# podstawa.net
KiCad netlist of a schematic drawn in EAGLE
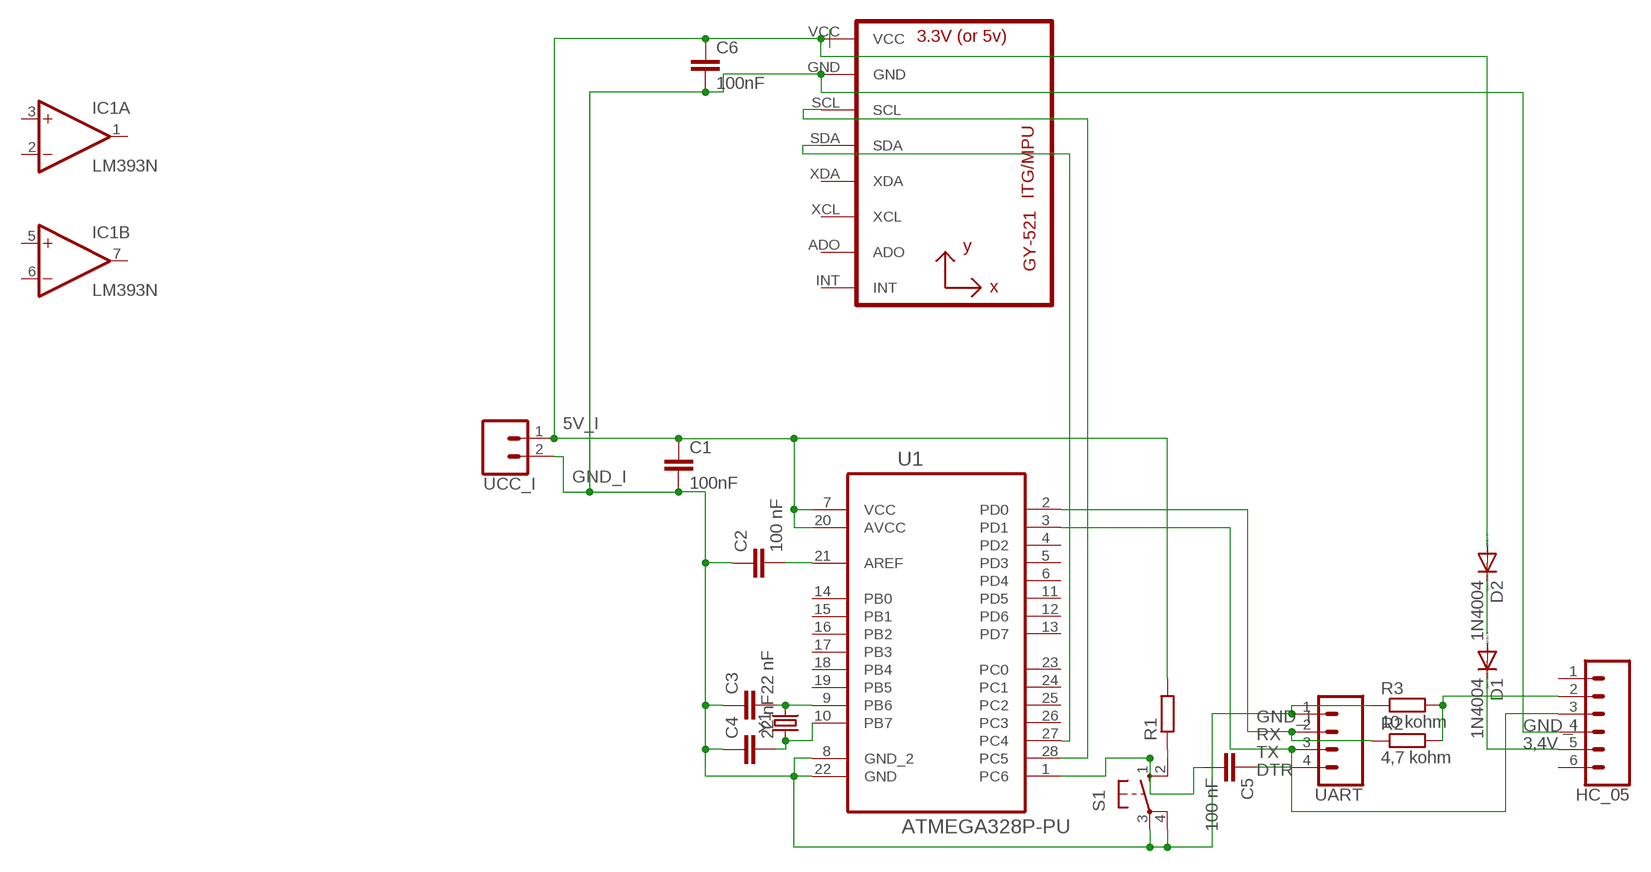
[diagram p0: schematic, sheet 1]

(export (version "E")
  (design (tool "Eeschema 10.0.6"))
  (components
    (comp (ref "C1")
      (value "100nF")
      (footprint "eagle-import:C025-030X050")
      (libsource (lib "eagle-import") (part "C-EU025-030X050"))
    )
    (comp (ref "C2")
      (value "100 nF")
      (footprint "eagle-import:C025-030X050")
      (libsource (lib "eagle-import") (part "C-EU025-030X050"))
    )
    (comp (ref "C3")
      (value "22 nF")
      (footprint "eagle-import:C025-030X050")
      (libsource (lib "eagle-import") (part "C-EU025-030X050"))
    )
    (comp (ref "C4")
      (value "22 nF")
      (footprint "eagle-import:C025-030X050")
      (libsource (lib "eagle-import") (part "C-EU025-030X050"))
    )
    (comp (ref "C5")
      (value "100 nF")
      (footprint "eagle-import:C025-030X050")
      (libsource (lib "eagle-import") (part "C-EU025-030X050"))
    )
    (comp (ref "C6")
      (value "100nF")
      (footprint "eagle-import:C025-030X050")
      (libsource (lib "eagle-import") (part "C-EU025-030X050"))
    )
    (comp (ref "D1")
      (value "1N4004")
      (footprint "eagle-import:DO41-10")
      (libsource (lib "eagle-import") (part "1N4004"))
    )
    (comp (ref "D2")
      (value "1N4004")
      (footprint "eagle-import:DO41-10")
      (libsource (lib "eagle-import") (part "1N4004"))
    )
    (comp (ref "HC_05")
      (value "CONN_06LONGPADS")
      (footprint "eagle-import:1X06_LONGPADS")
      (libsource (lib "eagle-import") (part "CONN_06LONGPADS"))
    )
    (comp (ref "IC1")
      (value "LM393N")
      (footprint "eagle-import:DIL08")
      (libsource (lib "eagle-import") (part "LM393N"))
    )
    (comp (ref "R1")
      (value "R-EU_0204/7")
      (footprint "eagle-import:0204_7")
      (libsource (lib "eagle-import") (part "R-EU_0204/7"))
    )
    (comp (ref "R2")
      (value "4,7 kohm")
      (footprint "eagle-import:0207_10")
      (libsource (lib "eagle-import") (part "R-EU_0207/10"))
    )
    (comp (ref "R3")
      (value "10 kohm")
      (footprint "eagle-import:0207_10")
      (libsource (lib "eagle-import") (part "R-EU_0207/10"))
    )
    (comp (ref "S1")
      (value "10-XX")
      (footprint "eagle-import:B3F-10XX")
      (fields (field (name "MPN") "B3F-1000"))
      (libsource (lib "eagle-import") (part "10-XX"))
    )
    (comp (ref "U1")
      (value "ATMEGA328P-PU")
      (footprint "eagle-import:DIP254P762X457-28")
      (libsource (lib "eagle-import") (part "ATMEGA328P-PU"))
    )
    (comp (ref "U2")
      (value "GY-521MPU6050")
      (footprint "eagle-import:GY-521")
      (libsource (lib "eagle-import") (part "GY-521MPU6050"))
    )
    (comp (ref "UART")
      (value "CONN_04LOCK_LONGPADS")
      (footprint "eagle-import:1X04_LOCK_LONGPADS")
      (libsource (lib "eagle-import") (part "CONN_04LOCK_LONGPADS"))
    )
    (comp (ref "UCC_I")
      (value "CONN_02LOCK_LONGPADS")
      (footprint "eagle-import:1X02_LOCK_LONGPADS")
      (libsource (lib "eagle-import") (part "CONN_02LOCK_LONGPADS"))
    )
    (comp (ref "Y1")
      (value "CRYSTALPTH-HC49US")
      (footprint "eagle-import:HC49US")
      (libsource (lib "eagle-import") (part "CRYSTALPTH-HC49US"))
    )
  )
  (nets
    (net (code "1") (name "/3,4V") (class "Default")
      (node (ref "D1") (pin "C") (pinfunction "C_C") (pintype "passive"))
      (node (ref "HC_05") (pin "5") (pinfunction "5_5") (pintype "passive"))
    )
    (net (code "2") (name "/5V_I") (class "Default")
      (node (ref "C1") (pin "1") (pinfunction "1_1") (pintype "passive"))
      (node (ref "C6") (pin "1") (pinfunction "1_1") (pintype "passive"))
      (node (ref "D2") (pin "A") (pinfunction "A_A") (pintype "passive"))
      (node (ref "R1") (pin "2") (pinfunction "2_2") (pintype "passive"))
      (node (ref "U1") (pin "20") (pinfunction "AVCC_20") (pintype "power_in"))
      (node (ref "U1") (pin "7") (pinfunction "VCC_7") (pintype "power_in"))
      (node (ref "U2") (pin "VCC") (pinfunction "VCC_VCC") (pintype "bidirectional"))
      (node (ref "UCC_I") (pin "1") (pinfunction "1_1") (pintype "passive"))
    )
    (net (code "3") (name "/DTR") (class "Default")
      (node (ref "C5") (pin "1") (pinfunction "1_1") (pintype "passive"))
      (node (ref "UART") (pin "4") (pinfunction "4_4") (pintype "passive"))
    )
    (net (code "4") (name "/GND_I") (class "Default")
      (node (ref "C1") (pin "2") (pinfunction "2_2") (pintype "passive"))
      (node (ref "C2") (pin "1") (pinfunction "1_1") (pintype "passive"))
      (node (ref "C3") (pin "1") (pinfunction "1_1") (pintype "passive"))
      (node (ref "C4") (pin "1") (pinfunction "1_1") (pintype "passive"))
      (node (ref "C6") (pin "2") (pinfunction "2_2") (pintype "passive"))
      (node (ref "HC_05") (pin "4") (pinfunction "4_4") (pintype "passive"))
      (node (ref "R3") (pin "1") (pinfunction "1_1") (pintype "passive"))
      (node (ref "S1") (pin "3") (pinfunction "P_3") (pintype "passive"))
      (node (ref "S1") (pin "4") (pinfunction "P1_4") (pintype "passive"))
      (node (ref "U1") (pin "22") (pinfunction "GND_22") (pintype "passive"))
      (node (ref "U1") (pin "8") (pinfunction "GND_2_8") (pintype "passive"))
      (node (ref "U2") (pin "GND") (pinfunction "GND_GND") (pintype "bidirectional"))
      (node (ref "UART") (pin "1") (pinfunction "1_1") (pintype "passive"))
      (node (ref "UCC_I") (pin "2") (pinfunction "2_2") (pintype "passive"))
    )
    (net (code "5") (name "/RX") (class "Default")
      (node (ref "R2") (pin "1") (pinfunction "1_1") (pintype "passive"))
      (node (ref "U1") (pin "2") (pinfunction "PD0_2") (pintype "bidirectional"))
      (node (ref "UART") (pin "2") (pinfunction "2_2") (pintype "passive"))
    )
    (net (code "6") (name "/TX") (class "Default")
      (node (ref "HC_05") (pin "3") (pinfunction "3_3") (pintype "passive"))
      (node (ref "U1") (pin "3") (pinfunction "PD1_3") (pintype "bidirectional"))
      (node (ref "UART") (pin "3") (pinfunction "3_3") (pintype "passive"))
    )
    (net (code "7") (name "Net-(HC_05-Pad2)") (class "Default")
      (node (ref "HC_05") (pin "2") (pinfunction "2_2") (pintype "passive"))
      (node (ref "R2") (pin "2") (pinfunction "2_2") (pintype "passive"))
      (node (ref "R3") (pin "2") (pinfunction "2_2") (pintype "passive"))
    )
    (net (code "8") (name "Net-(S1-S)") (class "Default")
      (node (ref "C5") (pin "2") (pinfunction "2_2") (pintype "passive"))
      (node (ref "S1") (pin "1") (pinfunction "S_1") (pintype "passive"))
      (node (ref "U1") (pin "1") (pinfunction "PC6_1") (pintype "bidirectional"))
    )
    (net (code "9") (name "Net-(S1-S1)") (class "Default")
      (node (ref "R1") (pin "1") (pinfunction "1_1") (pintype "passive"))
      (node (ref "S1") (pin "2") (pinfunction "S1_2") (pintype "passive"))
    )
    (net (code "10") (name "Net-(U1-AREF)") (class "Default")
      (node (ref "C2") (pin "2") (pinfunction "2_2") (pintype "passive"))
      (node (ref "U1") (pin "21") (pinfunction "AREF_21") (pintype "input"))
    )
    (net (code "11") (name "Net-(U1-PB6)") (class "Default")
      (node (ref "C3") (pin "2") (pinfunction "2_2") (pintype "passive"))
      (node (ref "U1") (pin "9") (pinfunction "PB6_9") (pintype "bidirectional"))
      (node (ref "Y1") (pin "2") (pinfunction "2_2") (pintype "passive"))
    )
    (net (code "12") (name "Net-(U1-PB7)") (class "Default")
      (node (ref "C4") (pin "2") (pinfunction "2_2") (pintype "passive"))
      (node (ref "U1") (pin "10") (pinfunction "PB7_10") (pintype "bidirectional"))
      (node (ref "Y1") (pin "1") (pinfunction "1_1") (pintype "passive"))
    )
    (net (code "13") (name "Net-(U1-PC4)") (class "Default")
      (node (ref "U1") (pin "27") (pinfunction "PC4_27") (pintype "bidirectional"))
      (node (ref "U2") (pin "SDA") (pinfunction "SDA_SDA") (pintype "bidirectional"))
    )
    (net (code "14") (name "Net-(U1-PC5)") (class "Default")
      (node (ref "U1") (pin "28") (pinfunction "PC5_28") (pintype "bidirectional"))
      (node (ref "U2") (pin "SCL") (pinfunction "SCL_SCL") (pintype "bidirectional"))
    )
    (net (code "15") (name "unconnected-(D1-PadA)") (class "Default")
      (node (ref "D1") (pin "A") (pinfunction "A_A") (pintype "passive"))
    )
    (net (code "16") (name "unconnected-(D2-PadC)") (class "Default")
      (node (ref "D2") (pin "C") (pinfunction "C_C") (pintype "passive"))
    )
    (net (code "17") (name "unconnected-(HC_05-Pad1)") (class "Default")
      (node (ref "HC_05") (pin "1") (pinfunction "1_1") (pintype "passive"))
    )
    (net (code "18") (name "unconnected-(HC_05-Pad6)") (class "Default")
      (node (ref "HC_05") (pin "6") (pinfunction "6_6") (pintype "passive"))
    )
    (net (code "19") (name "unconnected-(IC1A-+IN-Pad3)") (class "Default")
      (node (ref "IC1") (pin "3") (pinfunction "+IN_3") (pintype "input"))
    )
    (net (code "20") (name "unconnected-(IC1A--IN-Pad2)") (class "Default")
      (node (ref "IC1") (pin "2") (pinfunction "-IN_2") (pintype "input"))
    )
    (net (code "21") (name "unconnected-(IC1A-OUT-Pad1)") (class "Default")
      (node (ref "IC1") (pin "1") (pinfunction "OUT_1") (pintype "output"))
    )
    (net (code "22") (name "unconnected-(IC1B-+IN-Pad5)") (class "Default")
      (node (ref "IC1") (pin "5") (pinfunction "+IN_5") (pintype "input"))
    )
    (net (code "23") (name "unconnected-(IC1B--IN-Pad6)") (class "Default")
      (node (ref "IC1") (pin "6") (pinfunction "-IN_6") (pintype "input"))
    )
    (net (code "24") (name "unconnected-(IC1B-OUT-Pad7)") (class "Default")
      (node (ref "IC1") (pin "7") (pinfunction "OUT_7") (pintype "output"))
    )
    (net (code "25") (name "unconnected-(U1-PB0-Pad14)") (class "Default")
      (node (ref "U1") (pin "14") (pinfunction "PB0_14") (pintype "bidirectional"))
    )
    (net (code "26") (name "unconnected-(U1-PB1-Pad15)") (class "Default")
      (node (ref "U1") (pin "15") (pinfunction "PB1_15") (pintype "bidirectional"))
    )
    (net (code "27") (name "unconnected-(U1-PB2-Pad16)") (class "Default")
      (node (ref "U1") (pin "16") (pinfunction "PB2_16") (pintype "bidirectional"))
    )
    (net (code "28") (name "unconnected-(U1-PB3-Pad17)") (class "Default")
      (node (ref "U1") (pin "17") (pinfunction "PB3_17") (pintype "bidirectional"))
    )
    (net (code "29") (name "unconnected-(U1-PB4-Pad18)") (class "Default")
      (node (ref "U1") (pin "18") (pinfunction "PB4_18") (pintype "bidirectional"))
    )
    (net (code "30") (name "unconnected-(U1-PB5-Pad19)") (class "Default")
      (node (ref "U1") (pin "19") (pinfunction "PB5_19") (pintype "bidirectional"))
    )
    (net (code "31") (name "unconnected-(U1-PC0-Pad23)") (class "Default")
      (node (ref "U1") (pin "23") (pinfunction "PC0_23") (pintype "bidirectional"))
    )
    (net (code "32") (name "unconnected-(U1-PC1-Pad24)") (class "Default")
      (node (ref "U1") (pin "24") (pinfunction "PC1_24") (pintype "bidirectional"))
    )
    (net (code "33") (name "unconnected-(U1-PC2-Pad25)") (class "Default")
      (node (ref "U1") (pin "25") (pinfunction "PC2_25") (pintype "bidirectional"))
    )
    (net (code "34") (name "unconnected-(U1-PC3-Pad26)") (class "Default")
      (node (ref "U1") (pin "26") (pinfunction "PC3_26") (pintype "bidirectional"))
    )
    (net (code "35") (name "unconnected-(U1-PD2-Pad4)") (class "Default")
      (node (ref "U1") (pin "4") (pinfunction "PD2_4") (pintype "bidirectional"))
    )
    (net (code "36") (name "unconnected-(U1-PD3-Pad5)") (class "Default")
      (node (ref "U1") (pin "5") (pinfunction "PD3_5") (pintype "bidirectional"))
    )
    (net (code "37") (name "unconnected-(U1-PD4-Pad6)") (class "Default")
      (node (ref "U1") (pin "6") (pinfunction "PD4_6") (pintype "bidirectional"))
    )
    (net (code "38") (name "unconnected-(U1-PD5-Pad11)") (class "Default")
      (node (ref "U1") (pin "11") (pinfunction "PD5_11") (pintype "bidirectional"))
    )
    (net (code "39") (name "unconnected-(U1-PD6-Pad12)") (class "Default")
      (node (ref "U1") (pin "12") (pinfunction "PD6_12") (pintype "bidirectional"))
    )
    (net (code "40") (name "unconnected-(U1-PD7-Pad13)") (class "Default")
      (node (ref "U1") (pin "13") (pinfunction "PD7_13") (pintype "bidirectional"))
    )
    (net (code "41") (name "unconnected-(U2-PadADO)") (class "Default")
      (node (ref "U2") (pin "ADO") (pinfunction "ADO_ADO") (pintype "bidirectional"))
    )
    (net (code "42") (name "unconnected-(U2-PadINT)") (class "Default")
      (node (ref "U2") (pin "INT") (pinfunction "INT_INT") (pintype "bidirectional"))
    )
    (net (code "43") (name "unconnected-(U2-PadXCL)") (class "Default")
      (node (ref "U2") (pin "XCL") (pinfunction "XCL_XCL") (pintype "bidirectional"))
    )
    (net (code "44") (name "unconnected-(U2-PadXDA)") (class "Default")
      (node (ref "U2") (pin "XDA") (pinfunction "XDA_XDA") (pintype "bidirectional"))
    )
  )
)
